# buck_module_12v.net
KiCad netlist of a schematic drawn in EAGLE
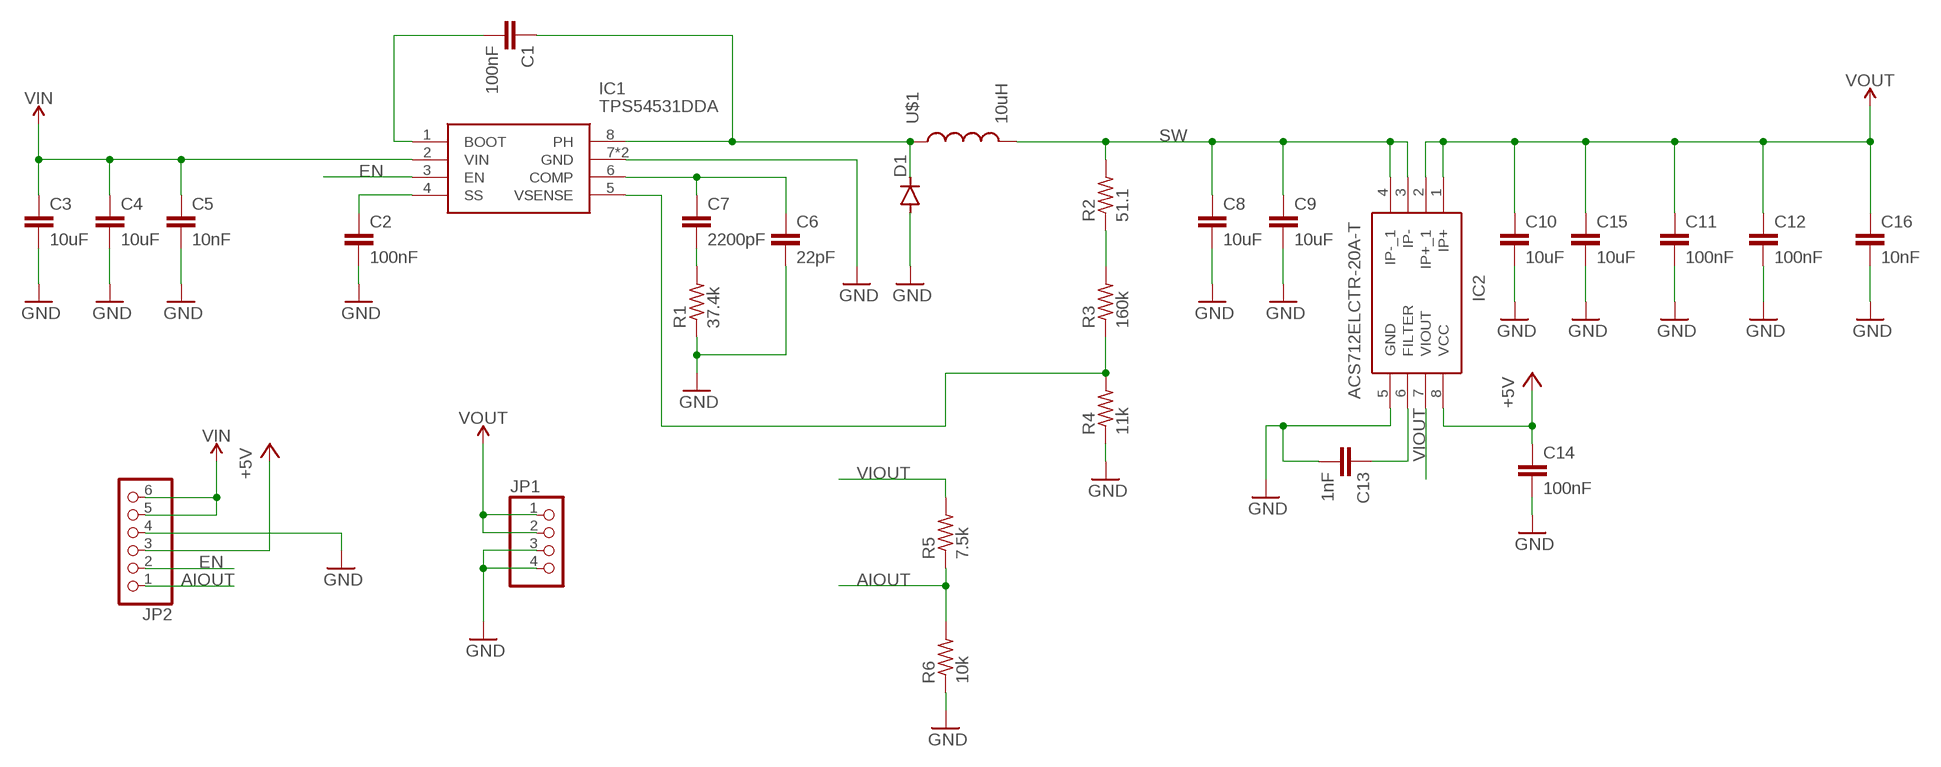
[diagram p0: schematic, sheet 1]

(export (version "E")
  (design (tool "Eeschema 10.0.6"))
  (components
    (comp (ref "C1")
      (value "100nF")
      (footprint "eagle-import:C0603")
      (libsource (lib "eagle-import") (part "C-EUC0603"))
    )
    (comp (ref "C2")
      (value "100nF")
      (footprint "eagle-import:C0603")
      (libsource (lib "eagle-import") (part "C-EUC0603"))
    )
    (comp (ref "C3")
      (value "10uF")
      (footprint "eagle-import:C1206")
      (libsource (lib "eagle-import") (part "C-EUC1206"))
    )
    (comp (ref "C4")
      (value "10uF")
      (footprint "eagle-import:C1206")
      (libsource (lib "eagle-import") (part "C-EUC1206"))
    )
    (comp (ref "C5")
      (value "10nF")
      (footprint "eagle-import:C0603")
      (libsource (lib "eagle-import") (part "C-EUC0603"))
    )
    (comp (ref "C6")
      (value "22pF")
      (footprint "eagle-import:C0603")
      (libsource (lib "eagle-import") (part "C-EUC0603"))
    )
    (comp (ref "C7")
      (value "2200pF")
      (footprint "eagle-import:C0603")
      (libsource (lib "eagle-import") (part "C-EUC0603"))
    )
    (comp (ref "C8")
      (value "10uF")
      (footprint "eagle-import:C1206")
      (libsource (lib "eagle-import") (part "C-EUC1206"))
    )
    (comp (ref "C9")
      (value "10uF")
      (footprint "eagle-import:C1206")
      (libsource (lib "eagle-import") (part "C-EUC1206"))
    )
    (comp (ref "C10")
      (value "10uF")
      (footprint "eagle-import:C1206")
      (libsource (lib "eagle-import") (part "C-EUC1206"))
    )
    (comp (ref "C11")
      (value "100nF")
      (footprint "eagle-import:C0603")
      (libsource (lib "eagle-import") (part "C-EUC0603"))
    )
    (comp (ref "C12")
      (value "100nF")
      (footprint "eagle-import:C0603")
      (libsource (lib "eagle-import") (part "C-EUC0603"))
    )
    (comp (ref "C13")
      (value "1nF")
      (footprint "eagle-import:C0603")
      (libsource (lib "eagle-import") (part "C-EUC0603"))
    )
    (comp (ref "C14")
      (value "100nF")
      (footprint "eagle-import:C0603")
      (libsource (lib "eagle-import") (part "C-EUC0603"))
    )
    (comp (ref "C15")
      (value "10uF")
      (footprint "eagle-import:C1206")
      (libsource (lib "eagle-import") (part "C-EUC1206"))
    )
    (comp (ref "C16")
      (value "10nF")
      (footprint "eagle-import:C0603")
      (libsource (lib "eagle-import") (part "C-EUC0603"))
    )
    (comp (ref "D1")
      (value "DIODE-DO214AA")
      (footprint "eagle-import:DO214AA")
      (libsource (lib "eagle-import") (part "DIODE-DO214AA"))
    )
    (comp (ref "IC1")
      (value "TPS54531DDA")
      (footprint "eagle-import:SOIC127P600X170-9N")
      (fields (field (name "MOUSER_PART_NUMBER") "595-TPS54531DDA"))
      (libsource (lib "eagle-import") (part "TPS54531DDA"))
    )
    (comp (ref "IC2")
      (value "ACS712ELCTR-20A-T")
      (footprint "eagle-import:SOIC127P600X175-8N")
      (fields (field (name "RS_PART_NUMBER") "6807135P"))
      (libsource (lib "eagle-import") (part "ACS712ELCTR-20A-T"))
    )
    (comp (ref "JP1")
      (value "PINHD-1X4")
      (footprint "eagle-import:1X04")
      (libsource (lib "eagle-import") (part "PINHD-1X4"))
    )
    (comp (ref "JP2")
      (value "PINHD-1X6")
      (footprint "eagle-import:1X06")
      (libsource (lib "eagle-import") (part "PINHD-1X6"))
    )
    (comp (ref "R1")
      (value "37.4k")
      (footprint "eagle-import:R0603")
      (libsource (lib "eagle-import") (part "R-US_R0603"))
    )
    (comp (ref "R2")
      (value "51.1")
      (footprint "eagle-import:R0603")
      (libsource (lib "eagle-import") (part "R-US_R0603"))
    )
    (comp (ref "R3")
      (value "160k")
      (footprint "eagle-import:R0603")
      (libsource (lib "eagle-import") (part "R-US_R0603"))
    )
    (comp (ref "R4")
      (value "11k")
      (footprint "eagle-import:R0603")
      (libsource (lib "eagle-import") (part "R-US_R0603"))
    )
    (comp (ref "R5")
      (value "7.5k")
      (footprint "eagle-import:R0603")
      (libsource (lib "eagle-import") (part "R-US_R0603"))
    )
    (comp (ref "R6")
      (value "10k")
      (footprint "eagle-import:R0603")
      (libsource (lib "eagle-import") (part "R-US_R0603"))
    )
    (comp (ref "U$1")
      (value "10uH")
      (footprint "eagle-import:22UH-1040-5A")
      (libsource (lib "eagle-import") (part "22UH-1040-5A"))
    )
  )
  (nets
    (net (code "1") (name "+5V") (class "Default")
      (node (ref "C14") (pin "1") (pinfunction "1_1") (pintype "passive"))
      (node (ref "IC2") (pin "8") (pinfunction "VCC_8") (pintype "power_in"))
      (node (ref "JP2") (pin "3") (pinfunction "3_3") (pintype "passive"))
    )
    (net (code "2") (name "/AIOUT") (class "Default")
      (node (ref "JP2") (pin "1") (pinfunction "1_1") (pintype "passive"))
      (node (ref "R5") (pin "1") (pinfunction "1_1") (pintype "passive"))
      (node (ref "R6") (pin "2") (pinfunction "2_2") (pintype "passive"))
    )
    (net (code "3") (name "/EN") (class "Default")
      (node (ref "IC1") (pin "3") (pinfunction "EN_3") (pintype "bidirectional"))
      (node (ref "JP2") (pin "2") (pinfunction "2_2") (pintype "passive"))
    )
    (net (code "4") (name "/SW") (class "Default")
      (node (ref "C8") (pin "1") (pinfunction "1_1") (pintype "passive"))
      (node (ref "C9") (pin "1") (pinfunction "1_1") (pintype "passive"))
      (node (ref "IC2") (pin "3") (pinfunction "IP-_3") (pintype "bidirectional"))
      (node (ref "IC2") (pin "4") (pinfunction "IP-_1_4") (pintype "bidirectional"))
      (node (ref "R2") (pin "2") (pinfunction "2_2") (pintype "passive"))
      (node (ref "U$1") (pin "P$2") (pinfunction "2_P$2") (pintype "passive"))
    )
    (net (code "5") (name "/VIOUT") (class "Default")
      (node (ref "IC2") (pin "7") (pinfunction "VIOUT_7") (pintype "bidirectional"))
      (node (ref "R5") (pin "2") (pinfunction "2_2") (pintype "passive"))
    )
    (net (code "6") (name "GND") (class "Default")
      (node (ref "C10") (pin "2") (pinfunction "2_2") (pintype "passive"))
      (node (ref "C11") (pin "2") (pinfunction "2_2") (pintype "passive"))
      (node (ref "C12") (pin "2") (pinfunction "2_2") (pintype "passive"))
      (node (ref "C13") (pin "2") (pinfunction "2_2") (pintype "passive"))
      (node (ref "C14") (pin "2") (pinfunction "2_2") (pintype "passive"))
      (node (ref "C15") (pin "2") (pinfunction "2_2") (pintype "passive"))
      (node (ref "C16") (pin "2") (pinfunction "2_2") (pintype "passive"))
      (node (ref "C2") (pin "2") (pinfunction "2_2") (pintype "passive"))
      (node (ref "C3") (pin "2") (pinfunction "2_2") (pintype "passive"))
      (node (ref "C4") (pin "2") (pinfunction "2_2") (pintype "passive"))
      (node (ref "C5") (pin "2") (pinfunction "2_2") (pintype "passive"))
      (node (ref "C6") (pin "2") (pinfunction "2_2") (pintype "passive"))
      (node (ref "C8") (pin "2") (pinfunction "2_2") (pintype "passive"))
      (node (ref "C9") (pin "2") (pinfunction "2_2") (pintype "passive"))
      (node (ref "D1") (pin "A") (pinfunction "A_A") (pintype "passive"))
      (node (ref "IC1") (pin "7") (pinfunction "GND_7") (pintype "bidirectional"))
      (node (ref "IC1") (pin "9") (pinfunction "GND_9") (pintype "bidirectional"))
      (node (ref "IC2") (pin "5") (pinfunction "GND_5") (pintype "power_in"))
      (node (ref "JP1") (pin "3") (pinfunction "3_3") (pintype "passive"))
      (node (ref "JP1") (pin "4") (pinfunction "4_4") (pintype "passive"))
      (node (ref "JP2") (pin "4") (pinfunction "4_4") (pintype "passive"))
      (node (ref "R1") (pin "1") (pinfunction "1_1") (pintype "passive"))
      (node (ref "R4") (pin "1") (pinfunction "1_1") (pintype "passive"))
      (node (ref "R6") (pin "1") (pinfunction "1_1") (pintype "passive"))
    )
    (net (code "7") (name "Net-(C7-Pad2)") (class "Default")
      (node (ref "C7") (pin "2") (pinfunction "2_2") (pintype "passive"))
      (node (ref "R1") (pin "2") (pinfunction "2_2") (pintype "passive"))
    )
    (net (code "8") (name "Net-(IC1-BOOT)") (class "Default")
      (node (ref "C1") (pin "2") (pinfunction "2_2") (pintype "passive"))
      (node (ref "IC1") (pin "1") (pinfunction "BOOT_1") (pintype "bidirectional"))
    )
    (net (code "9") (name "Net-(IC1-COMP)") (class "Default")
      (node (ref "C6") (pin "1") (pinfunction "1_1") (pintype "passive"))
      (node (ref "C7") (pin "1") (pinfunction "1_1") (pintype "passive"))
      (node (ref "IC1") (pin "6") (pinfunction "COMP_6") (pintype "bidirectional"))
    )
    (net (code "10") (name "Net-(IC1-PH)") (class "Default")
      (node (ref "C1") (pin "1") (pinfunction "1_1") (pintype "passive"))
      (node (ref "D1") (pin "C") (pinfunction "C_C") (pintype "passive"))
      (node (ref "IC1") (pin "8") (pinfunction "PH_8") (pintype "bidirectional"))
      (node (ref "U$1") (pin "P$1") (pinfunction "1_P$1") (pintype "passive"))
    )
    (net (code "11") (name "Net-(IC1-SS)") (class "Default")
      (node (ref "C2") (pin "1") (pinfunction "1_1") (pintype "passive"))
      (node (ref "IC1") (pin "4") (pinfunction "SS_4") (pintype "bidirectional"))
    )
    (net (code "12") (name "Net-(IC1-VSENSE)") (class "Default")
      (node (ref "IC1") (pin "5") (pinfunction "VSENSE_5") (pintype "bidirectional"))
      (node (ref "R3") (pin "1") (pinfunction "1_1") (pintype "passive"))
      (node (ref "R4") (pin "2") (pinfunction "2_2") (pintype "passive"))
    )
    (net (code "13") (name "Net-(IC2-FILTER)") (class "Default")
      (node (ref "C13") (pin "1") (pinfunction "1_1") (pintype "passive"))
      (node (ref "IC2") (pin "6") (pinfunction "FILTER_6") (pintype "bidirectional"))
    )
    (net (code "14") (name "Net-(R2-Pad1)") (class "Default")
      (node (ref "R2") (pin "1") (pinfunction "1_1") (pintype "passive"))
      (node (ref "R3") (pin "2") (pinfunction "2_2") (pintype "passive"))
    )
    (net (code "15") (name "VIN") (class "Default")
      (node (ref "C3") (pin "1") (pinfunction "1_1") (pintype "passive"))
      (node (ref "C4") (pin "1") (pinfunction "1_1") (pintype "passive"))
      (node (ref "C5") (pin "1") (pinfunction "1_1") (pintype "passive"))
      (node (ref "IC1") (pin "2") (pinfunction "VIN_2") (pintype "bidirectional"))
      (node (ref "JP2") (pin "5") (pinfunction "5_5") (pintype "passive"))
      (node (ref "JP2") (pin "6") (pinfunction "6_6") (pintype "passive"))
    )
    (net (code "16") (name "VOUT") (class "Default")
      (node (ref "C10") (pin "1") (pinfunction "1_1") (pintype "passive"))
      (node (ref "C11") (pin "1") (pinfunction "1_1") (pintype "passive"))
      (node (ref "C12") (pin "1") (pinfunction "1_1") (pintype "passive"))
      (node (ref "C15") (pin "1") (pinfunction "1_1") (pintype "passive"))
      (node (ref "C16") (pin "1") (pinfunction "1_1") (pintype "passive"))
      (node (ref "IC2") (pin "1") (pinfunction "IP+_1") (pintype "bidirectional"))
      (node (ref "IC2") (pin "2") (pinfunction "IP+_1_2") (pintype "bidirectional"))
      (node (ref "JP1") (pin "1") (pinfunction "1_1") (pintype "passive"))
      (node (ref "JP1") (pin "2") (pinfunction "2_2") (pintype "passive"))
    )
  )
)
